# power_circuit2.net
KiCad netlist of a schematic drawn in EAGLE
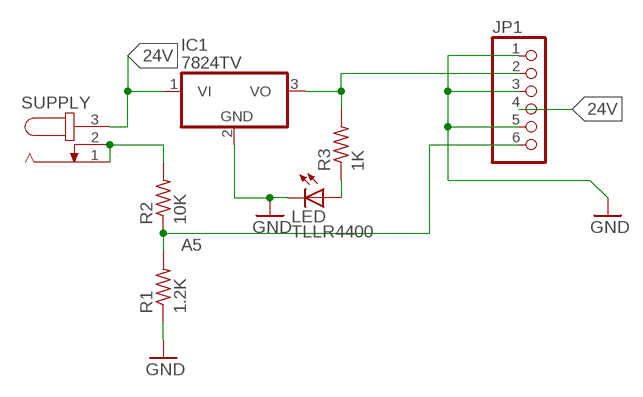
[diagram p0: schematic, sheet 1]

(export (version "E")
  (design (tool "Eeschema 10.0.6"))
  (components
    (comp (ref "IC1")
      (value "7824TV")
      (footprint "eagle-import:TO220V")
      (libsource (lib "eagle-import") (part "78TV24"))
    )
    (comp (ref "JP1")
      (value "PINHD-1X6B")
      (footprint "eagle-import:1X06-BIG")
      (libsource (lib "eagle-import") (part "PINHD-1X6B"))
    )
    (comp (ref "LED")
      (value "TLLR4400")
      (footprint "eagle-import:LED3MM")
      (fields (field (name "MF") "VISHAY SEMICONDUCTOR"))
      (libsource (lib "eagle-import") (part "TLLR4400"))
    )
    (comp (ref "R1")
      (value "1.2K")
      (footprint "eagle-import:0207_5V")
      (libsource (lib "eagle-import") (part "R-US_0207/5V"))
    )
    (comp (ref "R2")
      (value "10K")
      (footprint "eagle-import:0207_5V")
      (libsource (lib "eagle-import") (part "R-US_0207/5V"))
    )
    (comp (ref "R3")
      (value "1K")
      (footprint "eagle-import:0207_5V")
      (libsource (lib "eagle-import") (part "R-US_0207/5V"))
    )
    (comp (ref "SUPPLY")
      (value "JACK-PLUG1")
      (footprint "eagle-import:SPC4078")
      (libsource (lib "eagle-import") (part "JACK-PLUG1"))
    )
  )
  (nets
    (net (code "1") (name "/A5") (class "Default")
      (node (ref "JP1") (pin "6") (pinfunction "6_6") (pintype "passive"))
      (node (ref "R1") (pin "2") (pinfunction "2_2") (pintype "passive"))
      (node (ref "R2") (pin "1") (pinfunction "1_1") (pintype "passive"))
    )
    (net (code "2") (name "24V") (class "Default")
      (node (ref "IC1") (pin "1") (pinfunction "VI_1") (pintype "input"))
      (node (ref "JP1") (pin "4") (pinfunction "4_4") (pintype "passive"))
      (node (ref "SUPPLY") (pin "3") (pinfunction "3_3") (pintype "passive"))
    )
    (net (code "3") (name "GND") (class "Default")
      (node (ref "IC1") (pin "2") (pinfunction "GND_2") (pintype "passive"))
      (node (ref "JP1") (pin "1") (pinfunction "1_1") (pintype "passive"))
      (node (ref "JP1") (pin "3") (pinfunction "3_3") (pintype "passive"))
      (node (ref "JP1") (pin "5") (pinfunction "5_5") (pintype "passive"))
      (node (ref "LED") (pin "K") (pinfunction "C_K") (pintype "passive"))
      (node (ref "R1") (pin "1") (pinfunction "1_1") (pintype "passive"))
    )
    (net (code "4") (name "Net-(IC1-VO)") (class "Default")
      (node (ref "IC1") (pin "3") (pinfunction "VO_3") (pintype "passive"))
      (node (ref "JP1") (pin "2") (pinfunction "2_2") (pintype "passive"))
      (node (ref "R3") (pin "2") (pinfunction "2_2") (pintype "passive"))
    )
    (net (code "5") (name "Net-(LED-PadA)") (class "Default")
      (node (ref "LED") (pin "A") (pinfunction "A_A") (pintype "passive"))
      (node (ref "R3") (pin "1") (pinfunction "1_1") (pintype "passive"))
    )
    (net (code "6") (name "Net-(R2-Pad2)") (class "Default")
      (node (ref "R2") (pin "2") (pinfunction "2_2") (pintype "passive"))
      (node (ref "SUPPLY") (pin "1") (pinfunction "1_1") (pintype "passive"))
      (node (ref "SUPPLY") (pin "2") (pinfunction "2_2") (pintype "passive"))
    )
  )
)
